# Endstop.net
KiCad netlist of a schematic drawn in Altium Designer
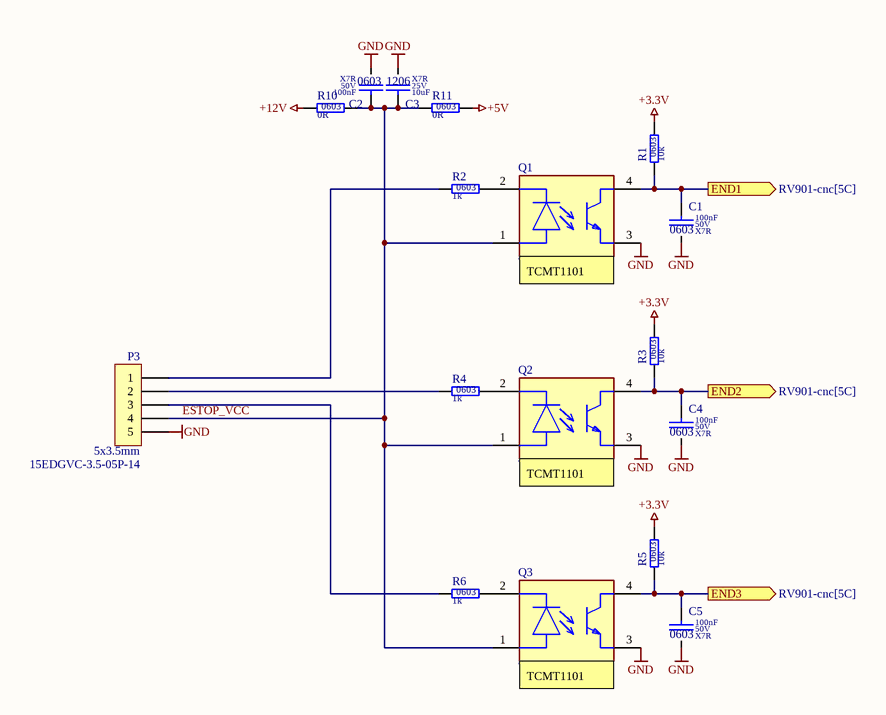
[diagram p0: Endstop.SchDoc]

(export (version "E")
  (design (tool "Eeschema 10.0.6"))
  (components
    (comp (ref "C1")
      (value "100nF")
      (footprint "C_0603_1608")
      (description "Capacitor")
      (fields
        (field (name "DIELECTRIC") "X7R")
        (field (name "VOLTAGE") "50V")
        (field (name "SCH_FOOTPRINT") "0603")
        (field (name "PART NUMBER") "C_100nF_50V_X7R_0603_5")
        (field (name "MANUFACTURER") "Samsung")
      )
      (libsource (lib "Library") (part "C"))
    )
    (comp (ref "C2")
      (value "100nF")
      (footprint "C_0603_1608")
      (description "Capacitor")
      (fields
        (field (name "DIELECTRIC") "X7R")
        (field (name "VOLTAGE") "50V")
        (field (name "SCH_FOOTPRINT") "0603")
        (field (name "PART NUMBER") "C_100nF_50V_X7R_0603_5")
        (field (name "MANUFACTURER") "Samsung")
      )
      (libsource (lib "Library") (part "C"))
    )
    (comp (ref "C3")
      (value "10uF")
      (footprint "C_1206_3216")
      (description "Capacitor")
      (fields
        (field (name "DIELECTRIC") "X7R")
        (field (name "VOLTAGE") "25V")
        (field (name "SCH_FOOTPRINT") "1206")
        (field (name "PART NUMBER") "C_10uF_25V_X7R_1206_10")
        (field (name "MANUFACTURER") "Samsung")
      )
      (libsource (lib "Library") (part "C"))
    )
    (comp (ref "C4")
      (value "100nF")
      (footprint "C_0603_1608")
      (description "Capacitor")
      (fields
        (field (name "DIELECTRIC") "X7R")
        (field (name "VOLTAGE") "50V")
        (field (name "SCH_FOOTPRINT") "0603")
        (field (name "PART NUMBER") "C_100nF_50V_X7R_0603_5")
        (field (name "MANUFACTURER") "Samsung")
      )
      (libsource (lib "Library") (part "C"))
    )
    (comp (ref "C5")
      (value "100nF")
      (footprint "C_0603_1608")
      (description "Capacitor")
      (fields
        (field (name "DIELECTRIC") "X7R")
        (field (name "VOLTAGE") "50V")
        (field (name "SCH_FOOTPRINT") "0603")
        (field (name "PART NUMBER") "C_100nF_50V_X7R_0603_5")
        (field (name "MANUFACTURER") "Samsung")
      )
      (libsource (lib "Library") (part "C"))
    )
    (comp (ref "P3")
      (value "15EDGVC-3.5-05P-14")
      (footprint "P_15EDGVC-3.5-05P")
      (description "Pin Header")
      (fields
        (field (name "SCH_FOOTPRINT") "5x3.5mm")
        (field (name "PART NUMBER") "P_15EDGVC-3.5-05P-14")
        (field (name "MANUFACTURER") "DEGSON ELECTRONICS")
      )
      (libsource (lib "Library") (part "P_HEADER_1x5"))
    )
    (comp (ref "Q1")
      (value "TCMT1106")
      (footprint "FP-TCMT1106-MFG")
      (fields (field (name "VOLTAGE") "6V"))
      (libsource (lib "Altium Content Vault") (part "e07288ace2826ef443abdfb88e741da"))
    )
    (comp (ref "Q2")
      (value "TCMT1106")
      (footprint "FP-TCMT1106-MFG")
      (fields (field (name "VOLTAGE") "6V"))
      (libsource (lib "Altium Content Vault") (part "e07288ace2826ef443abdfb88e741da"))
    )
    (comp (ref "Q3")
      (value "TCMT1106")
      (footprint "FP-TCMT1106-MFG")
      (fields (field (name "VOLTAGE") "6V"))
      (libsource (lib "Altium Content Vault") (part "e07288ace2826ef443abdfb88e741da"))
    )
    (comp (ref "R1")
      (value "10k")
      (footprint "R_0603_1608")
      (fields
        (field (name "SCH_FOOTPRINT") "0603")
        (field (name "PART NUMBER") "R_10k_0603_1_AECQ0")
        (field (name "VOLTAGE") "75V")
        (field (name "POWER") "100mW")
      )
      (libsource (lib "Library") (part "R"))
    )
    (comp (ref "R2")
      (value "1k")
      (footprint "R_0603_1608")
      (fields
        (field (name "SCH_FOOTPRINT") "0603")
        (field (name "PART NUMBER") "R_1k_0603_1_AECQ0")
        (field (name "VOLTAGE") "75V")
        (field (name "POWER") "100mW")
      )
      (libsource (lib "Library") (part "R"))
    )
    (comp (ref "R3")
      (value "10k")
      (footprint "R_0603_1608")
      (fields
        (field (name "SCH_FOOTPRINT") "0603")
        (field (name "PART NUMBER") "R_10k_0603_1_AECQ0")
        (field (name "VOLTAGE") "75V")
        (field (name "POWER") "100mW")
      )
      (libsource (lib "Library") (part "R"))
    )
    (comp (ref "R4")
      (value "1k")
      (footprint "R_0603_1608")
      (fields
        (field (name "SCH_FOOTPRINT") "0603")
        (field (name "PART NUMBER") "R_1k_0603_1_AECQ0")
        (field (name "VOLTAGE") "75V")
        (field (name "POWER") "100mW")
      )
      (libsource (lib "Library") (part "R"))
    )
    (comp (ref "R5")
      (value "10k")
      (footprint "R_0603_1608")
      (fields
        (field (name "SCH_FOOTPRINT") "0603")
        (field (name "PART NUMBER") "R_10k_0603_1_AECQ0")
        (field (name "VOLTAGE") "75V")
        (field (name "POWER") "100mW")
      )
      (libsource (lib "Library") (part "R"))
    )
    (comp (ref "R6")
      (value "1k")
      (footprint "R_0603_1608")
      (fields
        (field (name "SCH_FOOTPRINT") "0603")
        (field (name "PART NUMBER") "R_1k_0603_1_AECQ0")
        (field (name "VOLTAGE") "75V")
        (field (name "POWER") "100mW")
      )
      (libsource (lib "Library") (part "R"))
    )
    (comp (ref "R10")
      (value "0R")
      (footprint "R_0603_1608")
      (fields
        (field (name "SCH_FOOTPRINT") "0603")
        (field (name "PART NUMBER") "R_0R_0603_1")
        (field (name "VOLTAGE") "75V")
        (field (name "POWER") "100mW")
      )
      (libsource (lib "Library") (part "R"))
    )
    (comp (ref "R11")
      (value "0R")
      (footprint "R_0603_1608")
      (fields
        (field (name "SCH_FOOTPRINT") "0603")
        (field (name "PART NUMBER") "R_0R_0603_1")
        (field (name "VOLTAGE") "75V")
        (field (name "POWER") "100mW")
      )
      (libsource (lib "Library") (part "R"))
    )
  )
  (nets
    (net (code "1") (name "+3.3V") (class "Default")
      (node (ref "R1") (pin "2") (pinfunction "2_2") (pintype "passive"))
      (node (ref "R3") (pin "2") (pinfunction "2_2") (pintype "passive"))
      (node (ref "R5") (pin "2") (pinfunction "2_2") (pintype "passive"))
    )
    (net (code "2") (name "+5V") (class "Default")
      (node (ref "R11") (pin "2") (pinfunction "2_2") (pintype "passive"))
    )
    (net (code "3") (name "+12V") (class "Default")
      (node (ref "R10") (pin "1") (pinfunction "1_1") (pintype "passive"))
    )
    (net (code "4") (name "/END1") (class "Default")
      (node (ref "C1") (pin "1") (pinfunction "1_1") (pintype "passive"))
      (node (ref "Q1") (pin "4") (pinfunction "C_4") (pintype "passive"))
      (node (ref "R1") (pin "1") (pinfunction "1_1") (pintype "passive"))
    )
    (net (code "5") (name "/END2") (class "Default")
      (node (ref "C4") (pin "1") (pinfunction "1_1") (pintype "passive"))
      (node (ref "Q2") (pin "4") (pinfunction "C_4") (pintype "passive"))
      (node (ref "R3") (pin "1") (pinfunction "1_1") (pintype "passive"))
    )
    (net (code "6") (name "/END3") (class "Default")
      (node (ref "C5") (pin "1") (pinfunction "1_1") (pintype "passive"))
      (node (ref "Q3") (pin "4") (pinfunction "C_4") (pintype "passive"))
      (node (ref "R5") (pin "1") (pinfunction "1_1") (pintype "passive"))
    )
    (net (code "7") (name "/ESTOP_VCC") (class "Default")
      (node (ref "C2") (pin "1") (pinfunction "1_1") (pintype "passive"))
      (node (ref "C3") (pin "1") (pinfunction "1_1") (pintype "passive"))
      (node (ref "P3") (pin "4") (pinfunction "4_4") (pintype "passive"))
      (node (ref "Q1") (pin "1") (pinfunction "A_1") (pintype "passive"))
      (node (ref "Q2") (pin "1") (pinfunction "A_1") (pintype "passive"))
      (node (ref "Q3") (pin "1") (pinfunction "A_1") (pintype "passive"))
      (node (ref "R10") (pin "2") (pinfunction "2_2") (pintype "passive"))
      (node (ref "R11") (pin "1") (pinfunction "1_1") (pintype "passive"))
    )
    (net (code "8") (name "GND") (class "Default")
      (node (ref "C1") (pin "2") (pinfunction "2_2") (pintype "passive"))
      (node (ref "C2") (pin "2") (pinfunction "2_2") (pintype "passive"))
      (node (ref "C3") (pin "2") (pinfunction "2_2") (pintype "passive"))
      (node (ref "C4") (pin "2") (pinfunction "2_2") (pintype "passive"))
      (node (ref "C5") (pin "2") (pinfunction "2_2") (pintype "passive"))
      (node (ref "P3") (pin "5") (pinfunction "5_5") (pintype "passive"))
      (node (ref "Q1") (pin "3") (pinfunction "E_3") (pintype "passive"))
      (node (ref "Q2") (pin "3") (pinfunction "E_3") (pintype "passive"))
      (node (ref "Q3") (pin "3") (pinfunction "E_3") (pintype "passive"))
    )
    (net (code "9") (name "Net-(P3-Pad1)") (class "Default")
      (node (ref "P3") (pin "1") (pinfunction "1_1") (pintype "passive"))
      (node (ref "R2") (pin "1") (pinfunction "1_1") (pintype "passive"))
    )
    (net (code "10") (name "Net-(P3-Pad2)") (class "Default")
      (node (ref "P3") (pin "2") (pinfunction "2_2") (pintype "passive"))
      (node (ref "R4") (pin "1") (pinfunction "1_1") (pintype "passive"))
    )
    (net (code "11") (name "Net-(P3-Pad3)") (class "Default")
      (node (ref "P3") (pin "3") (pinfunction "3_3") (pintype "passive"))
      (node (ref "R6") (pin "1") (pinfunction "1_1") (pintype "passive"))
    )
    (net (code "12") (name "Net-(Q1-C-Pad2)") (class "Default")
      (node (ref "Q1") (pin "2") (pinfunction "C_2") (pintype "passive"))
      (node (ref "R2") (pin "2") (pinfunction "2_2") (pintype "passive"))
    )
    (net (code "13") (name "Net-(Q2-C-Pad2)") (class "Default")
      (node (ref "Q2") (pin "2") (pinfunction "C_2") (pintype "passive"))
      (node (ref "R4") (pin "2") (pinfunction "2_2") (pintype "passive"))
    )
    (net (code "14") (name "Net-(Q3-C-Pad2)") (class "Default")
      (node (ref "Q3") (pin "2") (pinfunction "C_2") (pintype "passive"))
      (node (ref "R6") (pin "2") (pinfunction "2_2") (pintype "passive"))
    )
  )
)
